# Ethernet_PHY.net
KiCad netlist of a schematic drawn in Altium Designer
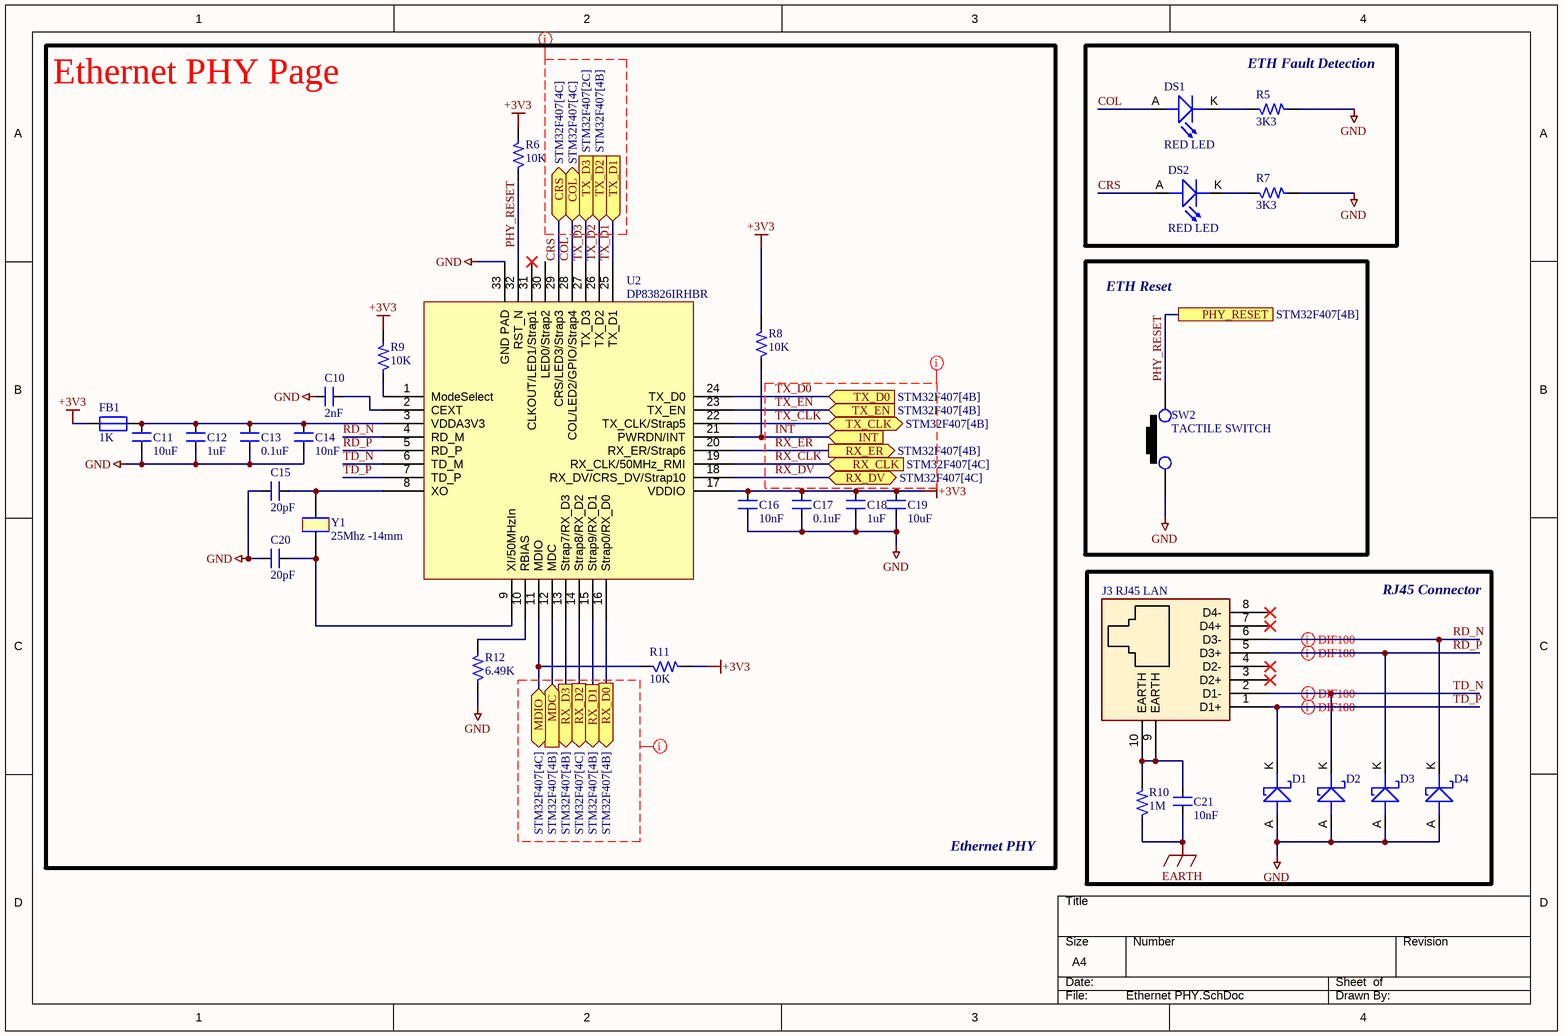
[diagram p0: Ethernet PHY.SchDoc]

(export (version "E")
  (design (tool "Eeschema 10.0.6"))
  (components
    (comp (ref "C10")
      (value "2nF")
      (footprint "CAP_0805")
      (description "2000pF ±10% 50V Ceramic Capacitor X7R 0805 (2012 Metric)")
      (fields
        (field (name "MANUFACTURER") "Samsung Electro-Mechanics")
        (field (name "MANUFACTURER PART NUMBER") "CL21B202KBANNNC")
      )
      (libsource (lib "ESTEEMPCBLIB") (part "CAP_2nF-50V-10%-0805"))
    )
    (comp (ref "C11")
      (value "10uF")
      (footprint "CAP_1206")
      (description "10µF ±10% 50V Ceramic Capacitor X7R 1206 (3216 Metric)")
      (fields
        (field (name "MANUFACTURER") "KEMET")
        (field (name "MANUFACTURER PART NUMBER") "CL31B106KBHNNNE")
      )
      (libsource (lib "ESTEEMPCBLIB") (part "CAP_10uF-50V-10%-1206"))
    )
    (comp (ref "C12")
      (value "1uF")
      (footprint "CAP_0805")
      (description "1µF ±5% 50V Ceramic Capacitor X7R 0805 (2012 Metric)")
      (fields
        (field (name "MANUFACTURER") "Samsung")
        (field (name "MANUFACTURER PART NUMBER") "CC0805JKX7R9BB105")
      )
      (libsource (lib "ESTEEMPCBLIB") (part "CAP_1uF-50V-5%-0805"))
    )
    (comp (ref "C13")
      (value "0.1uF")
      (footprint "CAP_0805")
      (description "0.1µF ±5% 50V Ceramic Capacitor X7R 0805 (2012 Metric)")
      (fields
        (field (name "MANUFACTURER") "AVX Corporation")
        (field (name "MANUFACTURER PART NUMBER") "08055C104JAT4A")
      )
      (libsource (lib "ESTEEMPCBLIB") (part "CAP_0.1uF-50V-5%-0805"))
    )
    (comp (ref "C14")
      (value "10nF")
      (footprint "CAP_0805")
      (description "10000pF ±10% 50V Ceramic Capacitor X7R 0805 (2012 Metric)")
      (fields
        (field (name "MANUFACTURER") "Samsung")
        (field (name "MANUFACTURER PART NUMBER") "C0805C103K5RECAUTO")
      )
      (libsource (lib "ESTEEMPCBLIB") (part "CAP_10nF-50V-10%-0805"))
    )
    (comp (ref "C15")
      (value "20pF")
      (footprint "CAP_0805")
      (description "±10% 50V Ceramic Capacitor C0G, NP0 0805 (2012 Metric)")
      (fields
        (field (name "MANUFACTURER") "AVX Corporation")
        (field (name "MANUFACTURER PART NUMBER") "08055A200KAT2A")
      )
      (libsource (lib "ESTEEMPCBLIB") (part "CAP_20pF-50V-10%-0805"))
    )
    (comp (ref "C16")
      (value "10nF")
      (footprint "CAP_0805")
      (description "10000pF ±10% 50V Ceramic Capacitor X7R 0805 (2012 Metric)")
      (fields
        (field (name "MANUFACTURER") "Samsung")
        (field (name "MANUFACTURER PART NUMBER") "C0805C103K5RECAUTO")
      )
      (libsource (lib "ESTEEMPCBLIB") (part "CAP_10nF-50V-10%-0805"))
    )
    (comp (ref "C17")
      (value "0.1uF")
      (footprint "CAP_0805")
      (description "0.1µF ±5% 50V Ceramic Capacitor X7R 0805 (2012 Metric)")
      (fields
        (field (name "MANUFACTURER") "AVX Corporation")
        (field (name "MANUFACTURER PART NUMBER") "08055C104JAT4A")
      )
      (libsource (lib "ESTEEMPCBLIB") (part "CAP_0.1uF-50V-5%-0805"))
    )
    (comp (ref "C18")
      (value "1uF")
      (footprint "CAP_0805")
      (description "1µF ±5% 50V Ceramic Capacitor X7R 0805 (2012 Metric)")
      (fields
        (field (name "MANUFACTURER") "Samsung")
        (field (name "MANUFACTURER PART NUMBER") "CC0805JKX7R9BB105")
      )
      (libsource (lib "ESTEEMPCBLIB") (part "CAP_1uF-50V-5%-0805"))
    )
    (comp (ref "C19")
      (value "10uF")
      (footprint "CAP_1206")
      (description "10µF ±10% 50V Ceramic Capacitor X7R 1206 (3216 Metric)")
      (fields
        (field (name "MANUFACTURER") "KEMET")
        (field (name "MANUFACTURER PART NUMBER") "CL31B106KBHNNNE")
      )
      (libsource (lib "ESTEEMPCBLIB") (part "CAP_10uF-50V-10%-1206"))
    )
    (comp (ref "C20")
      (value "20pF")
      (footprint "CAP_0805")
      (description "±10% 50V Ceramic Capacitor C0G, NP0 0805 (2012 Metric)")
      (fields
        (field (name "MANUFACTURER") "AVX Corporation")
        (field (name "MANUFACTURER PART NUMBER") "08055A200KAT2A")
      )
      (libsource (lib "ESTEEMPCBLIB") (part "CAP_20pF-50V-10%-0805"))
    )
    (comp (ref "C21")
      (value "10nF")
      (footprint "CAP_P196_102X287_H332_RAD_TH")
      (description "10000pF ±10% 1000V (1kV) Ceramic Capacitor X7R Radial")
      (fields
        (field (name "MANUFACTURER") "Yageo")
        (field (name "MANUFACTURER PART NUMBER") "RDER73A103K2K1H03B")
      )
      (libsource (lib "ESTEEMPCBLIB") (part "CAP_10nF-1KV-10%-RAD-TH"))
    )
    (comp (ref "D1")
      (value "ESD3V3D9-TP")
      (footprint "DIO_SOD-923")
      (description "8.8V Clamp 5A (8/20µs) Ipp Tvs Diode Surface Mount SOD-923")
      (fields (field (name "MANUFACTURER") "Micro Commercial Co"))
      (libsource (lib "ESTEEMPCBLIB") (part "DIO-T_3.3V-8.8V-SOD923"))
    )
    (comp (ref "D2")
      (value "ESD3V3D9-TP")
      (footprint "DIO_SOD-923")
      (description "8.8V Clamp 5A (8/20µs) Ipp Tvs Diode Surface Mount SOD-923")
      (fields (field (name "MANUFACTURER") "Micro Commercial Co"))
      (libsource (lib "ESTEEMPCBLIB") (part "DIO-T_3.3V-8.8V-SOD923"))
    )
    (comp (ref "D3")
      (value "ESD3V3D9-TP")
      (footprint "DIO_SOD-923")
      (description "8.8V Clamp 5A (8/20µs) Ipp Tvs Diode Surface Mount SOD-923")
      (fields (field (name "MANUFACTURER") "Micro Commercial Co"))
      (libsource (lib "ESTEEMPCBLIB") (part "DIO-T_3.3V-8.8V-SOD923"))
    )
    (comp (ref "D4")
      (value "ESD3V3D9-TP")
      (footprint "DIO_SOD-923")
      (description "8.8V Clamp 5A (8/20µs) Ipp Tvs Diode Surface Mount SOD-923")
      (fields (field (name "MANUFACTURER") "Micro Commercial Co"))
      (libsource (lib "ESTEEMPCBLIB") (part "DIO-T_3.3V-8.8V-SOD923"))
    )
    (comp (ref "DS1")
      (value "RED LED")
      (footprint "LED_0805")
      (description "Red 631nm LED Indication - Discrete 2V 0805 (2012 Metric)")
      (fields
        (field (name "MANUFACTURER") "Vishay Lite-On")
        (field (name "MANUFACTURER PART NUMBER") "LTST-C171KRKT")
      )
      (libsource (lib "ESTEEMPCBLIB") (part "LED_RED-2V-20mA-0805"))
    )
    (comp (ref "DS2")
      (value "RED LED")
      (footprint "LED_0805")
      (description "Red 631nm LED Indication - Discrete 2V 0805 (2012 Metric)")
      (fields
        (field (name "MANUFACTURER") "Vishay Lite-On")
        (field (name "MANUFACTURER PART NUMBER") "LTST-C171KRKT")
      )
      (libsource (lib "ESTEEMPCBLIB") (part "LED_RED-2V-20mA-0805"))
    )
    (comp (ref "FB1")
      (value "1K")
      (footprint "IND_0805")
      (description "1 kOhms @ 100MHz 1 Power Line Ferrite Bead 0805 (2012 Metric) 1.6A")
      (fields
        (field (name "MANUFACTURER") "Laird")
        (field (name "MANUFACTURER PART NUMBER") "BLM21SP102SH1D")
      )
      (libsource (lib "ESTEEMPCBLIB") (part "FB_1K-100MHZ-1.6A-0805"))
    )
    (comp (ref "J3")
      (value "RJ45 LAN")
      (footprint "CON10_P106_RJ45_TH_ST")
      (description "8 Pins, 2 Row 2.54mm Pitch, right angle Connector, male")
      (fields
        (field (name "MANUFACTURER") "Assmann")
        (field (name "MANUFACTURER PART NUMBER") "A-2004-2-4-LPS-N-R")
      )
      (libsource (lib "ESTEEMPCBLIB") (part "CON-SKT-RJ_8C8P-RA-TH"))
    )
    (comp (ref "R5")
      (value "3K3")
      (footprint "RES_0603")
      (description "3.3 kOhms ±1% 0.1W, 1/10W Chip Resistor 0603 (1608 Metric) Automotive AEC-Q200 Thick Film")
      (fields (field (name "MANUFACTURER") "Wilson") (field (name "MANUFACTURER PART NUMBER") "WR06X3301FTL"))
      (libsource (lib "ESTEEMPCBLIB") (part "RES_3.3K-0.1W-1%-0603"))
    )
    (comp (ref "R6")
      (value "10K")
      (footprint "RES_0805")
      (description "10 kOhms ±1% 0.125W, 1/8W Chip Resistor 0805 (2012 Metric) Automotive AEC-Q200 Thick Film")
      (fields (field (name "MANUFACTURER") "CTS") (field (name "MANUFACTURER PART NUMBER") "WR08X1002FTL"))
      (libsource (lib "ESTEEMPCBLIB") (part "RES_10K-0.125W-1%-0805"))
    )
    (comp (ref "R7")
      (value "3K3")
      (footprint "RES_0603")
      (description "3.3 kOhms ±1% 0.1W, 1/10W Chip Resistor 0603 (1608 Metric) Automotive AEC-Q200 Thick Film")
      (fields (field (name "MANUFACTURER") "Wilson") (field (name "MANUFACTURER PART NUMBER") "WR06X3301FTL"))
      (libsource (lib "ESTEEMPCBLIB") (part "RES_3.3K-0.1W-1%-0603"))
    )
    (comp (ref "R8")
      (value "10K")
      (footprint "RES_0603")
      (description "10 kOhms ±1% 0.1W, 1/10W Chip Resistor 0603 (1608 Metric) Automotive AEC-Q200 Thick Film")
      (fields (field (name "MANUFACTURER") "Walsin") (field (name "MANUFACTURER PART NUMBER") "WR06X1002FTL"))
      (libsource (lib "ESTEEMPCBLIB") (part "RES_10K-0.1W-1%-0603"))
    )
    (comp (ref "R9")
      (value "10K")
      (footprint "RES_0805")
      (description "10 kOhms ±1% 0.125W, 1/8W Chip Resistor 0805 (2012 Metric) Automotive AEC-Q200 Thick Film")
      (fields (field (name "MANUFACTURER") "CTS") (field (name "MANUFACTURER PART NUMBER") "WR08X1002FTL"))
      (libsource (lib "ESTEEMPCBLIB") (part "RES_10K-0.125W-1%-0805"))
    )
    (comp (ref "R10")
      (value "1M")
      (footprint "RES_0805")
      (description "1 MOhms ±1% 0.125W, 1/8W Chip Resistor 0805 (2012 Metric) Automotive AEC-Q200 Thick Film")
      (fields (field (name "MANUFACTURER") "Walsin") (field (name "MANUFACTURER PART NUMBER") "WR08X1004FTL"))
      (libsource (lib "ESTEEMPCBLIB") (part "RES_1M-0.125W-1%-0805"))
    )
    (comp (ref "R11")
      (value "10K")
      (footprint "RES_0805")
      (description "10 kOhms ±1% 0.125W, 1/8W Chip Resistor 0805 (2012 Metric) Automotive AEC-Q200 Thick Film")
      (fields (field (name "MANUFACTURER") "CTS") (field (name "MANUFACTURER PART NUMBER") "WR08X1002FTL"))
      (libsource (lib "ESTEEMPCBLIB") (part "RES_10K-0.125W-1%-0805"))
    )
    (comp (ref "R12")
      (value "6.49K")
      (footprint "RES_0805")
      (description "6.49 kOhms ±1% 0.125W, 1/8W Chip Resistor 0805 (2012 Metric) Moisture Resistant Thick Film")
      (fields
        (field (name "MANUFACTURER") "Stackpole Electronics")
        (field (name "MANUFACTURER PART NUMBER") "RC0805FR-076K49L")
      )
      (libsource (lib "ESTEEMPCBLIB") (part "RES_6.49K-0.125W-1%-0805"))
    )
    (comp (ref "SW2")
      (value "TACTILE SWITCH")
      (footprint "SW_342_SMD")
      (description "Tactile Switch SPST-NO Top Actuated Surface Mount")
      (fields
        (field (name "MANUFACTURER") "ITT C&K")
        (field (name "MANUFACTURER PART NUMBER") "RS-282G05A3-SMRT")
      )
      (libsource (lib "ESTEEMPCBLIB") (part "SW1_RS-282G05A3-SMRT-SMD"))
    )
    (comp (ref "U2")
      (value "DP83826IRHBR")
      (footprint "VQFN32_19_218_23X9_SMD")
      (fields (field (name "MANUFACTURER") "Texas Instruments"))
      (libsource (lib "ESTEEMPCBLIB") (part "IC_DP83826IRHBR"))
    )
    (comp (ref "Y1")
      (value "25Mhz -14mm")
      (footprint "XTAL_314_240X47_SMD")
      (description "25MHz ±30ppm Crystal 20pF 30 Ohms HC-49/US")
      (fields
        (field (name "MANUFACTURER") "Abracon")
        (field (name "MANUFACTURER PART NUMBER") "FOXSDLF/250F-20")
      )
      (libsource (lib "ESTEEMPCBLIB") (part "XTAL_25Mhz-FOXSDLF/250F-20"))
    )
  )
  (nets
    (net (code "1") (name "+3V3") (class "Default")
      (node (ref "C16") (pin "2") (pinfunction "2_2") (pintype "passive"))
      (node (ref "C17") (pin "2") (pinfunction "2_2") (pintype "passive"))
      (node (ref "C18") (pin "2") (pinfunction "2_2") (pintype "passive"))
      (node (ref "C19") (pin "2") (pinfunction "2_2") (pintype "passive"))
      (node (ref "FB1") (pin "1") (pinfunction "1_1") (pintype "passive"))
      (node (ref "R11") (pin "2") (pinfunction "2_2") (pintype "passive"))
      (node (ref "R6") (pin "2") (pinfunction "2_2") (pintype "passive"))
      (node (ref "R8") (pin "2") (pinfunction "2_2") (pintype "passive"))
      (node (ref "R9") (pin "2") (pinfunction "2_2") (pintype "passive"))
      (node (ref "U2") (pin "17") (pinfunction "VDDIO_17") (pintype "passive"))
    )
    (net (code "2") (name "/COL") (class "Default")
      (node (ref "DS1") (pin "A") (pinfunction "ANODE_A") (pintype "passive"))
      (node (ref "U2") (pin "28") (pinfunction "COL/LED2/GPIO/Strap4_28") (pintype "passive"))
    )
    (net (code "3") (name "/CRS") (class "Default")
      (node (ref "DS2") (pin "A") (pinfunction "ANODE_A") (pintype "passive"))
      (node (ref "U2") (pin "29") (pinfunction "CRS/LED3/Strap3_29") (pintype "passive"))
    )
    (net (code "4") (name "/INT") (class "Default")
      (node (ref "R8") (pin "1") (pinfunction "1_1") (pintype "passive"))
      (node (ref "U2") (pin "21") (pinfunction "PWRDN/INT_21") (pintype "passive"))
    )
    (net (code "5") (name "/MDC") (class "Default")
      (node (ref "U2") (pin "12") (pinfunction "MDC_12") (pintype "passive"))
    )
    (net (code "6") (name "/MDIO") (class "Default")
      (node (ref "R11") (pin "1") (pinfunction "1_1") (pintype "passive"))
      (node (ref "U2") (pin "11") (pinfunction "MDIO_11") (pintype "passive"))
    )
    (net (code "7") (name "/PHY_RESET") (class "Default")
      (node (ref "R6") (pin "1") (pinfunction "1_1") (pintype "passive"))
      (node (ref "SW2") (pin "2") (pinfunction "2_2") (pintype "passive"))
      (node (ref "U2") (pin "32") (pinfunction "RST_N_32") (pintype "passive"))
    )
    (net (code "8") (name "/RD_N") (class "Default")
      (node (ref "D4") (pin "K") (pinfunction "K_K") (pintype "passive"))
      (node (ref "J3") (pin "6") (pinfunction "D3-_6") (pintype "passive"))
      (node (ref "U2") (pin "4") (pinfunction "RD_M_4") (pintype "passive"))
    )
    (net (code "9") (name "/RD_P") (class "Default")
      (node (ref "D3") (pin "K") (pinfunction "K_K") (pintype "passive"))
      (node (ref "J3") (pin "5") (pinfunction "D3+_5") (pintype "passive"))
      (node (ref "U2") (pin "5") (pinfunction "RD_P_5") (pintype "passive"))
    )
    (net (code "10") (name "/RX_CLK") (class "Default")
      (node (ref "U2") (pin "19") (pinfunction "RX_CLK/50MHz_RMI_19") (pintype "passive"))
    )
    (net (code "11") (name "/RX_D0") (class "Default")
      (node (ref "U2") (pin "16") (pinfunction "Strap0/RX_D0_16") (pintype "passive"))
    )
    (net (code "12") (name "/RX_D1") (class "Default")
      (node (ref "U2") (pin "15") (pinfunction "Strap9/RX_D1_15") (pintype "passive"))
    )
    (net (code "13") (name "/RX_D2") (class "Default")
      (node (ref "U2") (pin "14") (pinfunction "Strap8/RX_D2_14") (pintype "passive"))
    )
    (net (code "14") (name "/RX_D3") (class "Default")
      (node (ref "U2") (pin "13") (pinfunction "Strap7/RX_D3_13") (pintype "passive"))
    )
    (net (code "15") (name "/RX_DV") (class "Default")
      (node (ref "U2") (pin "18") (pinfunction "RX_DV/CRS_DV/Strap10_18") (pintype "passive"))
    )
    (net (code "16") (name "/RX_ER") (class "Default")
      (node (ref "U2") (pin "20") (pinfunction "RX_ER/Strap6_20") (pintype "passive"))
    )
    (net (code "17") (name "/TD_N") (class "Default")
      (node (ref "D2") (pin "K") (pinfunction "K_K") (pintype "passive"))
      (node (ref "J3") (pin "2") (pinfunction "D1-_2") (pintype "passive"))
      (node (ref "U2") (pin "6") (pinfunction "TD_M_6") (pintype "passive"))
    )
    (net (code "18") (name "/TD_P") (class "Default")
      (node (ref "D1") (pin "K") (pinfunction "K_K") (pintype "passive"))
      (node (ref "J3") (pin "1") (pinfunction "D1+_1") (pintype "passive"))
      (node (ref "U2") (pin "7") (pinfunction "TD_P_7") (pintype "passive"))
    )
    (net (code "19") (name "/TX_CLK") (class "Default")
      (node (ref "U2") (pin "22") (pinfunction "TX_CLK/Strap5_22") (pintype "passive"))
    )
    (net (code "20") (name "/TX_D0") (class "Default")
      (node (ref "U2") (pin "24") (pinfunction "TX_D0_24") (pintype "passive"))
    )
    (net (code "21") (name "/TX_D1") (class "Default")
      (node (ref "U2") (pin "25") (pinfunction "TX_D1_25") (pintype "passive"))
    )
    (net (code "22") (name "/TX_D2") (class "Default")
      (node (ref "U2") (pin "26") (pinfunction "TX_D2_26") (pintype "passive"))
    )
    (net (code "23") (name "/TX_D3") (class "Default")
      (node (ref "U2") (pin "27") (pinfunction "TX_D3_27") (pintype "passive"))
    )
    (net (code "24") (name "/TX_EN") (class "Default")
      (node (ref "U2") (pin "23") (pinfunction "TX_EN_23") (pintype "passive"))
    )
    (net (code "25") (name "EARTH") (class "Default")
      (node (ref "C21") (pin "1") (pinfunction "1_1") (pintype "passive"))
      (node (ref "R10") (pin "1") (pinfunction "1_1") (pintype "passive"))
    )
    (net (code "26") (name "GND") (class "Default")
      (node (ref "C10") (pin "1") (pinfunction "1_1") (pintype "passive"))
      (node (ref "C11") (pin "1") (pinfunction "1_1") (pintype "passive"))
      (node (ref "C12") (pin "1") (pinfunction "1_1") (pintype "passive"))
      (node (ref "C13") (pin "1") (pinfunction "1_1") (pintype "passive"))
      (node (ref "C14") (pin "1") (pinfunction "1_1") (pintype "passive"))
      (node (ref "C15") (pin "1") (pinfunction "1_1") (pintype "passive"))
      (node (ref "C16") (pin "1") (pinfunction "1_1") (pintype "passive"))
      (node (ref "C17") (pin "1") (pinfunction "1_1") (pintype "passive"))
      (node (ref "C18") (pin "1") (pinfunction "1_1") (pintype "passive"))
      (node (ref "C19") (pin "1") (pinfunction "1_1") (pintype "passive"))
      (node (ref "C20") (pin "1") (pinfunction "1_1") (pintype "passive"))
      (node (ref "D1") (pin "A") (pinfunction "A_A") (pintype "passive"))
      (node (ref "D2") (pin "A") (pinfunction "A_A") (pintype "passive"))
      (node (ref "D3") (pin "A") (pinfunction "A_A") (pintype "passive"))
      (node (ref "D4") (pin "A") (pinfunction "A_A") (pintype "passive"))
      (node (ref "R12") (pin "1") (pinfunction "1_1") (pintype "passive"))
      (node (ref "R5") (pin "2") (pinfunction "2_2") (pintype "passive"))
      (node (ref "R7") (pin "2") (pinfunction "2_2") (pintype "passive"))
      (node (ref "SW2") (pin "1") (pinfunction "1_1") (pintype "passive"))
      (node (ref "U2") (pin "33") (pinfunction "GND_PAD_33") (pintype "passive"))
    )
    (net (code "27") (name "Net-(C21-Pad2)") (class "Default")
      (node (ref "C21") (pin "2") (pinfunction "2_2") (pintype "passive"))
      (node (ref "J3") (pin "10") (pinfunction "EARTH_10") (pintype "passive"))
      (node (ref "J3") (pin "9") (pinfunction "EARTH_9") (pintype "passive"))
      (node (ref "R10") (pin "2") (pinfunction "2_2") (pintype "passive"))
    )
    (net (code "28") (name "Net-(DS1-CATHODE)") (class "Default")
      (node (ref "DS1") (pin "K") (pinfunction "CATHODE_K") (pintype "passive"))
      (node (ref "R5") (pin "1") (pinfunction "1_1") (pintype "passive"))
    )
    (net (code "29") (name "Net-(DS2-CATHODE)") (class "Default")
      (node (ref "DS2") (pin "K") (pinfunction "CATHODE_K") (pintype "passive"))
      (node (ref "R7") (pin "1") (pinfunction "1_1") (pintype "passive"))
    )
    (net (code "30") (name "Net-(U2-CEXT)") (class "Default")
      (node (ref "C10") (pin "2") (pinfunction "2_2") (pintype "passive"))
      (node (ref "U2") (pin "2") (pinfunction "CEXT_2") (pintype "passive"))
    )
    (net (code "31") (name "Net-(U2-ModeSelect)") (class "Default")
      (node (ref "R9") (pin "1") (pinfunction "1_1") (pintype "passive"))
      (node (ref "U2") (pin "1") (pinfunction "ModeSelect_1") (pintype "passive"))
    )
    (net (code "32") (name "Net-(U2-RBIAS)") (class "Default")
      (node (ref "R12") (pin "2") (pinfunction "2_2") (pintype "passive"))
      (node (ref "U2") (pin "10") (pinfunction "RBIAS_10") (pintype "passive"))
    )
    (net (code "33") (name "Net-(U2-VDDA3V3)") (class "Default")
      (node (ref "C11") (pin "2") (pinfunction "2_2") (pintype "passive"))
      (node (ref "C12") (pin "2") (pinfunction "2_2") (pintype "passive"))
      (node (ref "C13") (pin "2") (pinfunction "2_2") (pintype "passive"))
      (node (ref "C14") (pin "2") (pinfunction "2_2") (pintype "passive"))
      (node (ref "FB1") (pin "2") (pinfunction "2_2") (pintype "passive"))
      (node (ref "U2") (pin "3") (pinfunction "VDDA3V3_3") (pintype "passive"))
    )
    (net (code "34") (name "Net-(U2-XI{slash}50MHzIn)") (class "Default")
      (node (ref "C20") (pin "2") (pinfunction "2_2") (pintype "passive"))
      (node (ref "U2") (pin "9") (pinfunction "XI/50MHzIn_9") (pintype "passive"))
      (node (ref "Y1") (pin "1") (pinfunction "1_1") (pintype "passive"))
    )
    (net (code "35") (name "Net-(U2-XO)") (class "Default")
      (node (ref "C15") (pin "2") (pinfunction "2_2") (pintype "passive"))
      (node (ref "U2") (pin "8") (pinfunction "XO_8") (pintype "passive"))
      (node (ref "Y1") (pin "2") (pinfunction "2_2") (pintype "passive"))
    )
    (net (code "36") (name "unconnected-(J3-D2+-Pad3)") (class "Default")
      (node (ref "J3") (pin "3") (pinfunction "D2+_3") (pintype "passive+no_connect"))
    )
    (net (code "37") (name "unconnected-(J3-D2--Pad4)") (class "Default")
      (node (ref "J3") (pin "4") (pinfunction "D2-_4") (pintype "passive+no_connect"))
    )
    (net (code "38") (name "unconnected-(J3-D4+-Pad7)") (class "Default")
      (node (ref "J3") (pin "7") (pinfunction "D4+_7") (pintype "passive+no_connect"))
    )
    (net (code "39") (name "unconnected-(J3-D4--Pad8)") (class "Default")
      (node (ref "J3") (pin "8") (pinfunction "D4-_8") (pintype "passive+no_connect"))
    )
    (net (code "40") (name "unconnected-(U2-CLKOUT{slash}LED1{slash}Strap1-Pad31)") (class "Default")
      (node (ref "U2") (pin "31") (pinfunction "CLKOUT/LED1/Strap1_31") (pintype "passive+no_connect"))
    )
    (net (code "41") (name "unconnected-(U2-LED0{slash}Strap2-Pad30)") (class "Default")
      (node (ref "U2") (pin "30") (pinfunction "LED0/Strap2_30") (pintype "passive"))
    )
  )
)
